# atWork_Power2.net
KiCad netlist of a schematic drawn in Altium Designer
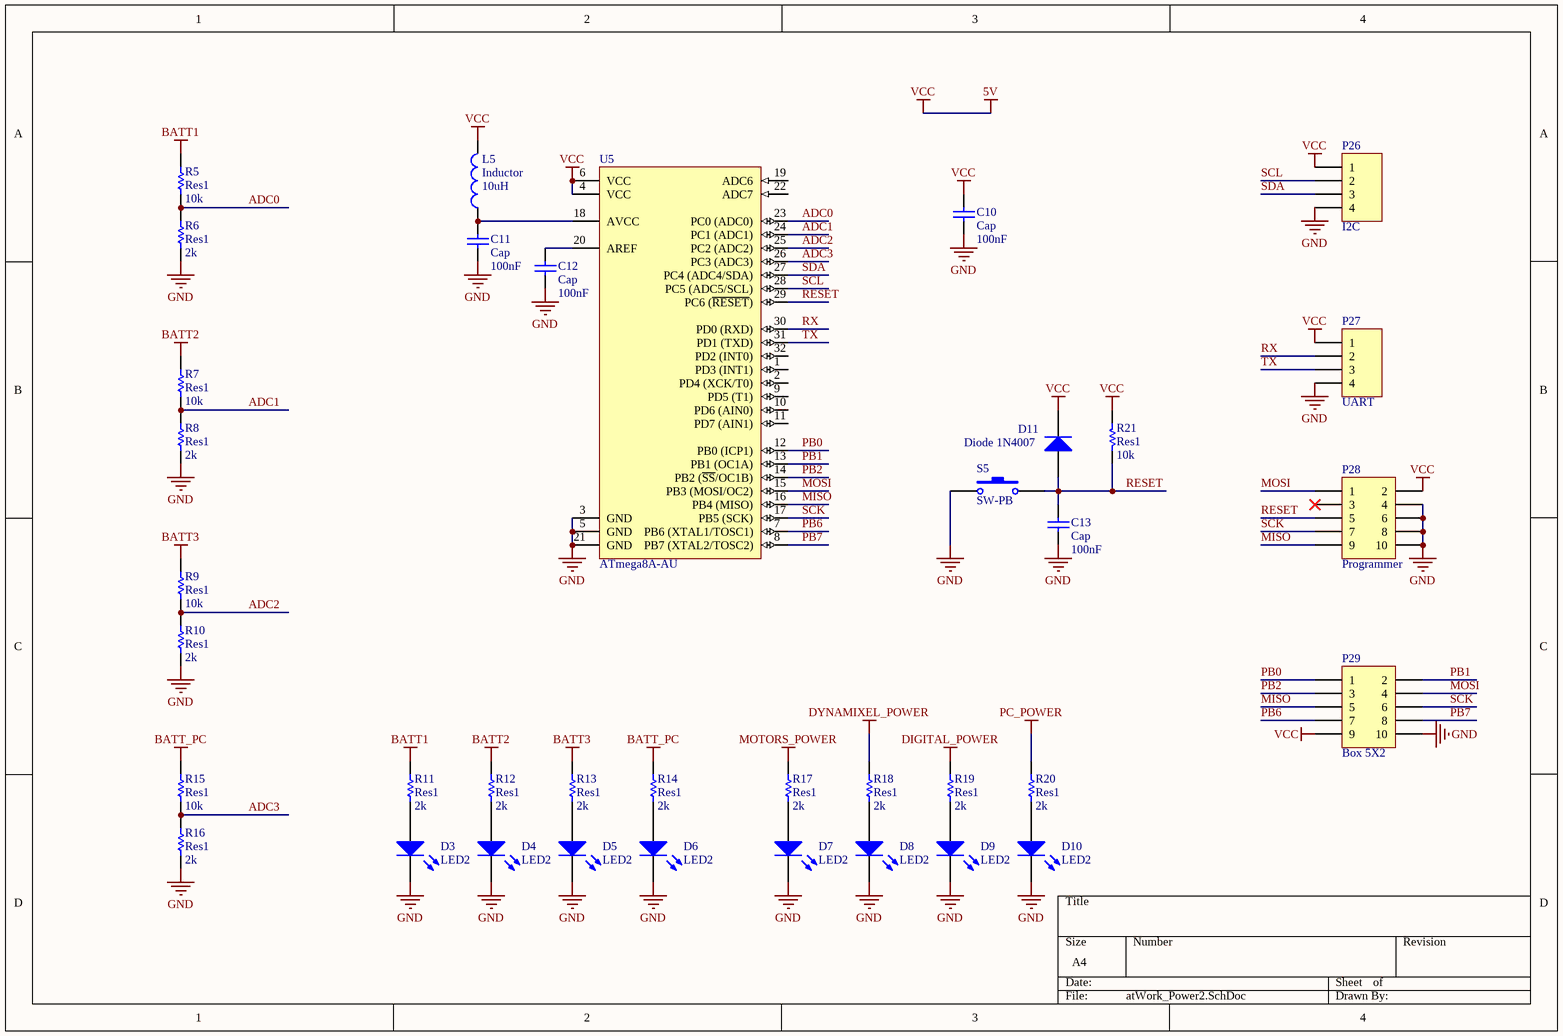
[diagram p0: atWork_Power2.SchDoc]

(export (version "E")
  (design (tool "Eeschema 10.0.6"))
  (components
    (comp (ref "C10")
      (value "Cap")
      (footprint "C1206")
      (description "Capacitor")
      (fields (field (name "ALTIUM_VALUE") "100nF") (field (name "PUBLISHER") "Altium Limited"))
      (libsource (lib "Miscellaneous Devices") (part "Cap"))
    )
    (comp (ref "C11")
      (value "Cap")
      (footprint "C1206")
      (description "Capacitor")
      (fields (field (name "ALTIUM_VALUE") "100nF") (field (name "PUBLISHER") "Altium Limited"))
      (libsource (lib "Miscellaneous Devices") (part "Cap"))
    )
    (comp (ref "C12")
      (value "Cap")
      (footprint "C1206")
      (description "Capacitor")
      (fields (field (name "ALTIUM_VALUE") "100nF") (field (name "PUBLISHER") "Altium Limited"))
      (libsource (lib "Miscellaneous Devices") (part "Cap"))
    )
    (comp (ref "C13")
      (value "Cap")
      (footprint "C1206")
      (description "Capacitor")
      (fields (field (name "ALTIUM_VALUE") "100nF") (field (name "PUBLISHER") "Altium Limited"))
      (libsource (lib "Miscellaneous Devices") (part "Cap"))
    )
    (comp (ref "D3")
      (value "LED2")
      (footprint "3.2X1.6X1.1")
      (description "Typical RED, GREEN, YELLOW, AMBER GaAs LED")
      (fields (field (name "PUBLISHER") "Altium Limited"))
      (libsource (lib "Miscellaneous Devices") (part "LED2"))
    )
    (comp (ref "D4")
      (value "LED2")
      (footprint "3.2X1.6X1.1")
      (description "Typical RED, GREEN, YELLOW, AMBER GaAs LED")
      (fields (field (name "PUBLISHER") "Altium Limited"))
      (libsource (lib "Miscellaneous Devices") (part "LED2"))
    )
    (comp (ref "D5")
      (value "LED2")
      (footprint "3.2X1.6X1.1")
      (description "Typical RED, GREEN, YELLOW, AMBER GaAs LED")
      (fields (field (name "PUBLISHER") "Altium Limited"))
      (libsource (lib "Miscellaneous Devices") (part "LED2"))
    )
    (comp (ref "D6")
      (value "LED2")
      (footprint "3.2X1.6X1.1")
      (description "Typical RED, GREEN, YELLOW, AMBER GaAs LED")
      (fields (field (name "PUBLISHER") "Altium Limited"))
      (libsource (lib "Miscellaneous Devices") (part "LED2"))
    )
    (comp (ref "D7")
      (value "LED2")
      (footprint "3.2X1.6X1.1")
      (description "Typical RED, GREEN, YELLOW, AMBER GaAs LED")
      (fields (field (name "PUBLISHER") "Altium Limited"))
      (libsource (lib "Miscellaneous Devices") (part "LED2"))
    )
    (comp (ref "D8")
      (value "LED2")
      (footprint "3.2X1.6X1.1")
      (description "Typical RED, GREEN, YELLOW, AMBER GaAs LED")
      (fields (field (name "PUBLISHER") "Altium Limited"))
      (libsource (lib "Miscellaneous Devices") (part "LED2"))
    )
    (comp (ref "D9")
      (value "LED2")
      (footprint "3.2X1.6X1.1")
      (description "Typical RED, GREEN, YELLOW, AMBER GaAs LED")
      (fields (field (name "PUBLISHER") "Altium Limited"))
      (libsource (lib "Miscellaneous Devices") (part "LED2"))
    )
    (comp (ref "D10")
      (value "LED2")
      (footprint "3.2X1.6X1.1")
      (description "Typical RED, GREEN, YELLOW, AMBER GaAs LED")
      (fields (field (name "PUBLISHER") "Altium Limited"))
      (libsource (lib "Miscellaneous Devices") (part "LED2"))
    )
    (comp (ref "D11")
      (value "Diode 1N4007")
      (footprint "DIODE-SMD")
      (description "1 Amp General Purpose Rectifier")
      (fields (field (name "PUBLISHER") "Altium Limited"))
      (libsource (lib "Miscellaneous Devices") (part "Diode 1N4007"))
    )
    (comp (ref "L5")
      (value "Inductor")
      (footprint "C1206")
      (fields (field (name "ALTIUM_VALUE") "10uH") (field (name "PUBLISHER") "Altium Limited"))
      (libsource (lib "Miscellaneous Devices") (part "Inductor"))
    )
    (comp (ref "P26")
      (value "I2C")
      (footprint "XH4PIN")
      (description "Header, 4-Pin")
      (fields (field (name "PUBLISHER") "Altium Limited"))
      (libsource (lib "Miscellaneous Connectors") (part "Header 4"))
    )
    (comp (ref "P27")
      (value "UART")
      (footprint "XH4PIN")
      (description "Header, 4-Pin")
      (fields (field (name "PUBLISHER") "Altium Limited"))
      (libsource (lib "Miscellaneous Connectors") (part "Header 4"))
    )
    (comp (ref "P28")
      (value "Programmer")
      (footprint "BOX2X5")
      (description "Box, 5-Pin, Dual row")
      (fields (field (name "DESIGNER") "Meysam Parvizi") (field (name "EMAIL") "meysam.parvizi.ir@gmail.com"))
      (libsource (lib "mp") (part "Box 5X2"))
    )
    (comp (ref "P29")
      (value "Box 5X2")
      (footprint "BOX2X5")
      (description "Box, 5-Pin, Dual row")
      (fields (field (name "DESIGNER") "Meysam Parvizi") (field (name "EMAIL") "meysam.parvizi.ir@gmail.com"))
      (libsource (lib "mp") (part "Box 5X2"))
    )
    (comp (ref "R5")
      (value "Res1")
      (footprint "C1206")
      (description "Resistor")
      (fields (field (name "ALTIUM_VALUE") "10k") (field (name "PUBLISHER") "Altium Limited"))
      (libsource (lib "Miscellaneous Devices") (part "Res1"))
    )
    (comp (ref "R6")
      (value "Res1")
      (footprint "C1206")
      (description "Resistor")
      (fields (field (name "ALTIUM_VALUE") "2k") (field (name "PUBLISHER") "Altium Limited"))
      (libsource (lib "Miscellaneous Devices") (part "Res1"))
    )
    (comp (ref "R7")
      (value "Res1")
      (footprint "C1206")
      (description "Resistor")
      (fields (field (name "ALTIUM_VALUE") "10k") (field (name "PUBLISHER") "Altium Limited"))
      (libsource (lib "Miscellaneous Devices") (part "Res1"))
    )
    (comp (ref "R8")
      (value "Res1")
      (footprint "C1206")
      (description "Resistor")
      (fields (field (name "ALTIUM_VALUE") "2k") (field (name "PUBLISHER") "Altium Limited"))
      (libsource (lib "Miscellaneous Devices") (part "Res1"))
    )
    (comp (ref "R9")
      (value "Res1")
      (footprint "C1206")
      (description "Resistor")
      (fields (field (name "ALTIUM_VALUE") "10k") (field (name "PUBLISHER") "Altium Limited"))
      (libsource (lib "Miscellaneous Devices") (part "Res1"))
    )
    (comp (ref "R10")
      (value "Res1")
      (footprint "C1206")
      (description "Resistor")
      (fields (field (name "ALTIUM_VALUE") "2k") (field (name "PUBLISHER") "Altium Limited"))
      (libsource (lib "Miscellaneous Devices") (part "Res1"))
    )
    (comp (ref "R11")
      (value "Res1")
      (footprint "C1206")
      (description "Resistor")
      (fields (field (name "ALTIUM_VALUE") "2k") (field (name "PUBLISHER") "Altium Limited"))
      (libsource (lib "Miscellaneous Devices") (part "Res1"))
    )
    (comp (ref "R12")
      (value "Res1")
      (footprint "C1206")
      (description "Resistor")
      (fields (field (name "ALTIUM_VALUE") "2k") (field (name "PUBLISHER") "Altium Limited"))
      (libsource (lib "Miscellaneous Devices") (part "Res1"))
    )
    (comp (ref "R13")
      (value "Res1")
      (footprint "C1206")
      (description "Resistor")
      (fields (field (name "ALTIUM_VALUE") "2k") (field (name "PUBLISHER") "Altium Limited"))
      (libsource (lib "Miscellaneous Devices") (part "Res1"))
    )
    (comp (ref "R14")
      (value "Res1")
      (footprint "C1206")
      (description "Resistor")
      (fields (field (name "ALTIUM_VALUE") "2k") (field (name "PUBLISHER") "Altium Limited"))
      (libsource (lib "Miscellaneous Devices") (part "Res1"))
    )
    (comp (ref "R15")
      (value "Res1")
      (footprint "C1206")
      (description "Resistor")
      (fields (field (name "ALTIUM_VALUE") "10k") (field (name "PUBLISHER") "Altium Limited"))
      (libsource (lib "Miscellaneous Devices") (part "Res1"))
    )
    (comp (ref "R16")
      (value "Res1")
      (footprint "C1206")
      (description "Resistor")
      (fields (field (name "ALTIUM_VALUE") "2k") (field (name "PUBLISHER") "Altium Limited"))
      (libsource (lib "Miscellaneous Devices") (part "Res1"))
    )
    (comp (ref "R17")
      (value "Res1")
      (footprint "C1206")
      (description "Resistor")
      (fields (field (name "ALTIUM_VALUE") "2k") (field (name "PUBLISHER") "Altium Limited"))
      (libsource (lib "Miscellaneous Devices") (part "Res1"))
    )
    (comp (ref "R18")
      (value "Res1")
      (footprint "C1206")
      (description "Resistor")
      (fields (field (name "ALTIUM_VALUE") "2k") (field (name "PUBLISHER") "Altium Limited"))
      (libsource (lib "Miscellaneous Devices") (part "Res1"))
    )
    (comp (ref "R19")
      (value "Res1")
      (footprint "C1206")
      (description "Resistor")
      (fields (field (name "ALTIUM_VALUE") "2k") (field (name "PUBLISHER") "Altium Limited"))
      (libsource (lib "Miscellaneous Devices") (part "Res1"))
    )
    (comp (ref "R20")
      (value "Res1")
      (footprint "C1206")
      (description "Resistor")
      (fields (field (name "ALTIUM_VALUE") "2k") (field (name "PUBLISHER") "Altium Limited"))
      (libsource (lib "Miscellaneous Devices") (part "Res1"))
    )
    (comp (ref "R21")
      (value "Res1")
      (footprint "C1206")
      (description "Resistor")
      (fields (field (name "ALTIUM_VALUE") "10k") (field (name "PUBLISHER") "Altium Limited"))
      (libsource (lib "Miscellaneous Devices") (part "Res1"))
    )
    (comp (ref "S5")
      (value "SW-PB")
      (footprint "PUSH1")
      (description "Switch")
      (fields (field (name "PUBLISHER") "Altium Limited"))
      (libsource (lib "Miscellaneous Devices") (part "SW-PB"))
    )
    (comp (ref "U5")
      (value "ATmega8A-AU")
      (footprint "32A_M")
      (fields (field (name "PUBLISHER") "Altium Limited"))
      (libsource (lib "Atmel Microcontroller 8-Bit megaAVR") (part "ATmega8A-AU"))
    )
  )
  (nets
    (net (code "1") (name "/ADC0") (class "Default")
      (node (ref "R5") (pin "2") (pinfunction "2_2") (pintype "passive"))
      (node (ref "R6") (pin "1") (pinfunction "1_1") (pintype "passive"))
      (node (ref "U5") (pin "23") (pinfunction "PC0_(ADC0)_23") (pintype "bidirectional"))
    )
    (net (code "2") (name "/ADC1") (class "Default")
      (node (ref "R7") (pin "2") (pinfunction "2_2") (pintype "passive"))
      (node (ref "R8") (pin "1") (pinfunction "1_1") (pintype "passive"))
      (node (ref "U5") (pin "24") (pinfunction "PC1_(ADC1)_24") (pintype "bidirectional"))
    )
    (net (code "3") (name "/ADC2") (class "Default")
      (node (ref "R10") (pin "1") (pinfunction "1_1") (pintype "passive"))
      (node (ref "R9") (pin "2") (pinfunction "2_2") (pintype "passive"))
      (node (ref "U5") (pin "25") (pinfunction "PC2_(ADC2)_25") (pintype "bidirectional"))
    )
    (net (code "4") (name "/ADC3") (class "Default")
      (node (ref "R15") (pin "2") (pinfunction "2_2") (pintype "passive"))
      (node (ref "R16") (pin "1") (pinfunction "1_1") (pintype "passive"))
      (node (ref "U5") (pin "26") (pinfunction "PC3_(ADC3)_26") (pintype "bidirectional"))
    )
    (net (code "5") (name "/MISO") (class "Default")
      (node (ref "P28") (pin "9") (pinfunction "9_9") (pintype "passive"))
      (node (ref "P29") (pin "5") (pinfunction "5_5") (pintype "passive"))
      (node (ref "U5") (pin "16") (pinfunction "PB4_(MISO)_16") (pintype "bidirectional"))
    )
    (net (code "6") (name "/MOSI") (class "Default")
      (node (ref "P28") (pin "1") (pinfunction "1_1") (pintype "passive"))
      (node (ref "P29") (pin "4") (pinfunction "4_4") (pintype "passive"))
      (node (ref "U5") (pin "15") (pinfunction "PB3_(MOSI/OC2)_15") (pintype "bidirectional"))
    )
    (net (code "7") (name "/PB0") (class "Default")
      (node (ref "P29") (pin "1") (pinfunction "1_1") (pintype "passive"))
      (node (ref "U5") (pin "12") (pinfunction "PB0_(ICP1)_12") (pintype "bidirectional"))
    )
    (net (code "8") (name "/PB1") (class "Default")
      (node (ref "P29") (pin "2") (pinfunction "2_2") (pintype "passive"))
      (node (ref "U5") (pin "13") (pinfunction "PB1_(OC1A)_13") (pintype "bidirectional"))
    )
    (net (code "9") (name "/PB2") (class "Default")
      (node (ref "P29") (pin "3") (pinfunction "3_3") (pintype "passive"))
      (node (ref "U5") (pin "14") (pinfunction "PB2_(~{SS}/OC1B)_14") (pintype "bidirectional"))
    )
    (net (code "10") (name "/PB6") (class "Default")
      (node (ref "P29") (pin "7") (pinfunction "7_7") (pintype "passive"))
      (node (ref "U5") (pin "7") (pinfunction "PB6_(XTAL1/TOSC1)_7") (pintype "bidirectional"))
    )
    (net (code "11") (name "/PB7") (class "Default")
      (node (ref "P29") (pin "8") (pinfunction "8_8") (pintype "passive"))
      (node (ref "U5") (pin "8") (pinfunction "PB7_(XTAL2/TOSC2)_8") (pintype "bidirectional"))
    )
    (net (code "12") (name "/RESET") (class "Default")
      (node (ref "C13") (pin "2") (pinfunction "2_2") (pintype "passive"))
      (node (ref "D11") (pin "1") (pinfunction "A_1") (pintype "passive"))
      (node (ref "P28") (pin "5") (pinfunction "5_5") (pintype "passive"))
      (node (ref "R21") (pin "2") (pinfunction "2_2") (pintype "passive"))
      (node (ref "S5") (pin "1") (pinfunction "1_1") (pintype "passive"))
      (node (ref "U5") (pin "29") (pinfunction "PC6_(~{RESET})_29") (pintype "bidirectional"))
    )
    (net (code "13") (name "/RX") (class "Default")
      (node (ref "P27") (pin "2") (pinfunction "2_2") (pintype "passive"))
      (node (ref "U5") (pin "30") (pinfunction "PD0_(RXD)_30") (pintype "bidirectional"))
    )
    (net (code "14") (name "/SCK") (class "Default")
      (node (ref "P28") (pin "7") (pinfunction "7_7") (pintype "passive"))
      (node (ref "P29") (pin "6") (pinfunction "6_6") (pintype "passive"))
      (node (ref "U5") (pin "17") (pinfunction "PB5_(SCK)_17") (pintype "bidirectional"))
    )
    (net (code "15") (name "/SCL") (class "Default")
      (node (ref "P26") (pin "2") (pinfunction "2_2") (pintype "passive"))
      (node (ref "U5") (pin "28") (pinfunction "PC5_(ADC5/SCL)_28") (pintype "bidirectional"))
    )
    (net (code "16") (name "/SDA") (class "Default")
      (node (ref "P26") (pin "3") (pinfunction "3_3") (pintype "passive"))
      (node (ref "U5") (pin "27") (pinfunction "PC4_(ADC4/SDA)_27") (pintype "bidirectional"))
    )
    (net (code "17") (name "/TX") (class "Default")
      (node (ref "P27") (pin "3") (pinfunction "3_3") (pintype "passive"))
      (node (ref "U5") (pin "31") (pinfunction "PD1_(TXD)_31") (pintype "bidirectional"))
    )
    (net (code "18") (name "5V") (class "Default")
      (node (ref "C10") (pin "2") (pinfunction "2_2") (pintype "passive"))
      (node (ref "D11") (pin "2") (pinfunction "K_2") (pintype "passive"))
      (node (ref "L5") (pin "2") (pinfunction "2_2") (pintype "passive"))
      (node (ref "P26") (pin "1") (pinfunction "1_1") (pintype "passive"))
      (node (ref "P27") (pin "1") (pinfunction "1_1") (pintype "passive"))
      (node (ref "P28") (pin "2") (pinfunction "2_2") (pintype "passive"))
      (node (ref "P29") (pin "9") (pinfunction "9_9") (pintype "passive"))
      (node (ref "R21") (pin "1") (pinfunction "1_1") (pintype "passive"))
      (node (ref "U5") (pin "4") (pinfunction "VCC_4") (pintype "power_in"))
      (node (ref "U5") (pin "6") (pinfunction "VCC_6") (pintype "power_in"))
    )
    (net (code "19") (name "BATT1") (class "Default")
      (node (ref "R11") (pin "2") (pinfunction "2_2") (pintype "passive"))
      (node (ref "R5") (pin "1") (pinfunction "1_1") (pintype "passive"))
    )
    (net (code "20") (name "BATT2") (class "Default")
      (node (ref "R12") (pin "2") (pinfunction "2_2") (pintype "passive"))
      (node (ref "R7") (pin "1") (pinfunction "1_1") (pintype "passive"))
    )
    (net (code "21") (name "BATT3") (class "Default")
      (node (ref "R13") (pin "2") (pinfunction "2_2") (pintype "passive"))
      (node (ref "R9") (pin "1") (pinfunction "1_1") (pintype "passive"))
    )
    (net (code "22") (name "BATT_PC") (class "Default")
      (node (ref "R14") (pin "2") (pinfunction "2_2") (pintype "passive"))
      (node (ref "R15") (pin "1") (pinfunction "1_1") (pintype "passive"))
    )
    (net (code "23") (name "DIGITAL_POWER") (class "Default")
      (node (ref "R19") (pin "2") (pinfunction "2_2") (pintype "passive"))
    )
    (net (code "24") (name "DYNAMIXEL_POWER") (class "Default")
      (node (ref "R18") (pin "2") (pinfunction "2_2") (pintype "passive"))
    )
    (net (code "25") (name "GND") (class "Default")
      (node (ref "C10") (pin "1") (pinfunction "1_1") (pintype "passive"))
      (node (ref "C11") (pin "1") (pinfunction "1_1") (pintype "passive"))
      (node (ref "C12") (pin "1") (pinfunction "1_1") (pintype "passive"))
      (node (ref "C13") (pin "1") (pinfunction "1_1") (pintype "passive"))
      (node (ref "D10") (pin "2") (pinfunction "K_2") (pintype "passive"))
      (node (ref "D3") (pin "2") (pinfunction "K_2") (pintype "passive"))
      (node (ref "D4") (pin "2") (pinfunction "K_2") (pintype "passive"))
      (node (ref "D5") (pin "2") (pinfunction "K_2") (pintype "passive"))
      (node (ref "D6") (pin "2") (pinfunction "K_2") (pintype "passive"))
      (node (ref "D7") (pin "2") (pinfunction "K_2") (pintype "passive"))
      (node (ref "D8") (pin "2") (pinfunction "K_2") (pintype "passive"))
      (node (ref "D9") (pin "2") (pinfunction "K_2") (pintype "passive"))
      (node (ref "P26") (pin "4") (pinfunction "4_4") (pintype "passive"))
      (node (ref "P27") (pin "4") (pinfunction "4_4") (pintype "passive"))
      (node (ref "P28") (pin "10") (pinfunction "10_10") (pintype "passive"))
      (node (ref "P28") (pin "4") (pinfunction "4_4") (pintype "passive"))
      (node (ref "P28") (pin "6") (pinfunction "6_6") (pintype "passive"))
      (node (ref "P28") (pin "8") (pinfunction "8_8") (pintype "passive"))
      (node (ref "P29") (pin "10") (pinfunction "10_10") (pintype "passive"))
      (node (ref "R10") (pin "2") (pinfunction "2_2") (pintype "passive"))
      (node (ref "R16") (pin "2") (pinfunction "2_2") (pintype "passive"))
      (node (ref "R6") (pin "2") (pinfunction "2_2") (pintype "passive"))
      (node (ref "R8") (pin "2") (pinfunction "2_2") (pintype "passive"))
      (node (ref "S5") (pin "2") (pinfunction "2_2") (pintype "passive"))
      (node (ref "U5") (pin "21") (pinfunction "GND_21") (pintype "power_in"))
      (node (ref "U5") (pin "3") (pinfunction "GND_3") (pintype "power_in"))
      (node (ref "U5") (pin "5") (pinfunction "GND_5") (pintype "power_in"))
    )
    (net (code "26") (name "MOTORS_POWER") (class "Default")
      (node (ref "R17") (pin "2") (pinfunction "2_2") (pintype "passive"))
    )
    (net (code "27") (name "Net-(D3-A)") (class "Default")
      (node (ref "D3") (pin "1") (pinfunction "A_1") (pintype "passive"))
      (node (ref "R11") (pin "1") (pinfunction "1_1") (pintype "passive"))
    )
    (net (code "28") (name "Net-(D4-A)") (class "Default")
      (node (ref "D4") (pin "1") (pinfunction "A_1") (pintype "passive"))
      (node (ref "R12") (pin "1") (pinfunction "1_1") (pintype "passive"))
    )
    (net (code "29") (name "Net-(D5-A)") (class "Default")
      (node (ref "D5") (pin "1") (pinfunction "A_1") (pintype "passive"))
      (node (ref "R13") (pin "1") (pinfunction "1_1") (pintype "passive"))
    )
    (net (code "30") (name "Net-(D6-A)") (class "Default")
      (node (ref "D6") (pin "1") (pinfunction "A_1") (pintype "passive"))
      (node (ref "R14") (pin "1") (pinfunction "1_1") (pintype "passive"))
    )
    (net (code "31") (name "Net-(D7-A)") (class "Default")
      (node (ref "D7") (pin "1") (pinfunction "A_1") (pintype "passive"))
      (node (ref "R17") (pin "1") (pinfunction "1_1") (pintype "passive"))
    )
    (net (code "32") (name "Net-(D8-A)") (class "Default")
      (node (ref "D8") (pin "1") (pinfunction "A_1") (pintype "passive"))
      (node (ref "R18") (pin "1") (pinfunction "1_1") (pintype "passive"))
    )
    (net (code "33") (name "Net-(D9-A)") (class "Default")
      (node (ref "D9") (pin "1") (pinfunction "A_1") (pintype "passive"))
      (node (ref "R19") (pin "1") (pinfunction "1_1") (pintype "passive"))
    )
    (net (code "34") (name "Net-(D10-A)") (class "Default")
      (node (ref "D10") (pin "1") (pinfunction "A_1") (pintype "passive"))
      (node (ref "R20") (pin "1") (pinfunction "1_1") (pintype "passive"))
    )
    (net (code "35") (name "Net-(U5-AREF)") (class "Default")
      (node (ref "C12") (pin "2") (pinfunction "2_2") (pintype "passive"))
      (node (ref "U5") (pin "20") (pinfunction "AREF_20") (pintype "power_in"))
    )
    (net (code "36") (name "Net-(U5-AVCC)") (class "Default")
      (node (ref "C11") (pin "2") (pinfunction "2_2") (pintype "passive"))
      (node (ref "L5") (pin "1") (pinfunction "1_1") (pintype "passive"))
      (node (ref "U5") (pin "18") (pinfunction "AVCC_18") (pintype "power_in"))
    )
    (net (code "37") (name "PC_POWER") (class "Default")
      (node (ref "R20") (pin "2") (pinfunction "2_2") (pintype "passive"))
    )
    (net (code "38") (name "unconnected-(P28-Pad3)") (class "Default")
      (node (ref "P28") (pin "3") (pinfunction "3_3") (pintype "passive+no_connect"))
    )
    (net (code "39") (name "unconnected-(U5-ADC6-Pad19)") (class "Default")
      (node (ref "U5") (pin "19") (pinfunction "ADC6_19") (pintype "input"))
    )
    (net (code "40") (name "unconnected-(U5-ADC7-Pad22)") (class "Default")
      (node (ref "U5") (pin "22") (pinfunction "ADC7_22") (pintype "input"))
    )
    (net (code "41") (name "unconnected-(U5-PD2_(INT0)-Pad32)") (class "Default")
      (node (ref "U5") (pin "32") (pinfunction "PD2_(INT0)_32") (pintype "bidirectional"))
    )
    (net (code "42") (name "unconnected-(U5-PD3_(INT1)-Pad1)") (class "Default")
      (node (ref "U5") (pin "1") (pinfunction "PD3_(INT1)_1") (pintype "bidirectional"))
    )
    (net (code "43") (name "unconnected-(U5-PD4_(XCK{slash}T0)-Pad2)") (class "Default")
      (node (ref "U5") (pin "2") (pinfunction "PD4_(XCK/T0)_2") (pintype "bidirectional"))
    )
    (net (code "44") (name "unconnected-(U5-PD5_(T1)-Pad9)") (class "Default")
      (node (ref "U5") (pin "9") (pinfunction "PD5_(T1)_9") (pintype "bidirectional"))
    )
    (net (code "45") (name "unconnected-(U5-PD6_(AIN0)-Pad10)") (class "Default")
      (node (ref "U5") (pin "10") (pinfunction "PD6_(AIN0)_10") (pintype "bidirectional"))
    )
    (net (code "46") (name "unconnected-(U5-PD7_(AIN1)-Pad11)") (class "Default")
      (node (ref "U5") (pin "11") (pinfunction "PD7_(AIN1)_11") (pintype "bidirectional"))
    )
  )
)
